# EEPROM_breakout.net
KiCad netlist of a schematic drawn in EAGLE
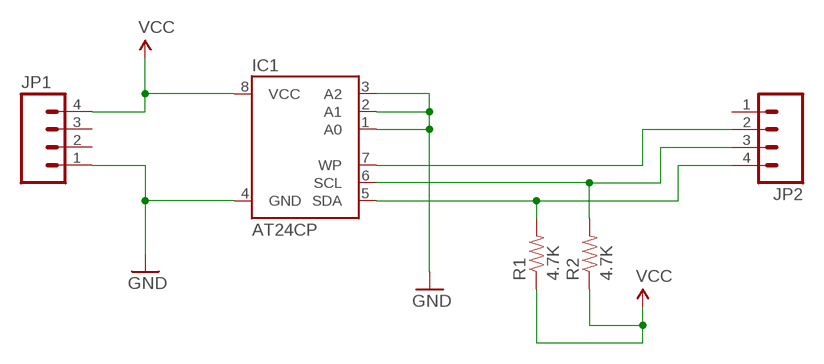
[diagram p0: schematic, sheet 1]

(export (version "E")
  (design (tool "Eeschema 10.0.6"))
  (components
    (comp (ref "IC1")
      (value "AT24CP")
      (footprint "eagle-import:DIL08")
      (fields (field (name "MPN") "AT24C1024BW-SH-B"))
      (libsource (lib "eagle-import") (part "AT24CP"))
    )
    (comp (ref "JP1")
      (value "M04LOCK")
      (footprint "eagle-import:1X04_LOCK")
      (libsource (lib "eagle-import") (part "M04LOCK"))
    )
    (comp (ref "JP2")
      (value "M04LOCK")
      (footprint "eagle-import:1X04_LOCK")
      (libsource (lib "eagle-import") (part "M04LOCK"))
    )
    (comp (ref "R1")
      (value "4.7K")
      (footprint "eagle-import:AXIAL-0.4")
      (libsource (lib "eagle-import") (part "RESISTORPTH-1/4W"))
    )
    (comp (ref "R2")
      (value "4.7K")
      (footprint "eagle-import:AXIAL-0.4")
      (libsource (lib "eagle-import") (part "RESISTORPTH-1/4W"))
    )
  )
  (nets
    (net (code "1") (name "GND") (class "Default")
      (node (ref "IC1") (pin "1") (pinfunction "A0_1") (pintype "input"))
      (node (ref "IC1") (pin "2") (pinfunction "A1_2") (pintype "input"))
      (node (ref "IC1") (pin "3") (pinfunction "A2_3") (pintype "input"))
      (node (ref "IC1") (pin "4") (pinfunction "GND_4") (pintype "power_in"))
      (node (ref "JP1") (pin "1") (pinfunction "1_1") (pintype "passive"))
    )
    (net (code "2") (name "Net-(IC1-SCL)") (class "Default")
      (node (ref "IC1") (pin "6") (pinfunction "SCL_6") (pintype "bidirectional"))
      (node (ref "JP2") (pin "3") (pinfunction "3_3") (pintype "passive"))
      (node (ref "R2") (pin "P$2") (pinfunction "2_P$2") (pintype "passive"))
    )
    (net (code "3") (name "Net-(IC1-SDA)") (class "Default")
      (node (ref "IC1") (pin "5") (pinfunction "SDA_5") (pintype "bidirectional"))
      (node (ref "JP2") (pin "4") (pinfunction "4_4") (pintype "passive"))
      (node (ref "R1") (pin "P$2") (pinfunction "2_P$2") (pintype "passive"))
    )
    (net (code "4") (name "Net-(IC1-WP)") (class "Default")
      (node (ref "IC1") (pin "7") (pinfunction "WP_7") (pintype "input"))
      (node (ref "JP2") (pin "2") (pinfunction "2_2") (pintype "passive"))
    )
    (net (code "5") (name "VCC") (class "Default")
      (node (ref "IC1") (pin "8") (pinfunction "VCC_8") (pintype "power_in"))
      (node (ref "JP1") (pin "4") (pinfunction "4_4") (pintype "passive"))
      (node (ref "R1") (pin "P$1") (pinfunction "1_P$1") (pintype "passive"))
      (node (ref "R2") (pin "P$1") (pinfunction "1_P$1") (pintype "passive"))
    )
    (net (code "6") (name "unconnected-(JP1-Pad2)") (class "Default")
      (node (ref "JP1") (pin "2") (pinfunction "2_2") (pintype "passive"))
    )
    (net (code "7") (name "unconnected-(JP1-Pad3)") (class "Default")
      (node (ref "JP1") (pin "3") (pinfunction "3_3") (pintype "passive"))
    )
    (net (code "8") (name "unconnected-(JP2-Pad1)") (class "Default")
      (node (ref "JP2") (pin "1") (pinfunction "1_1") (pintype "passive"))
    )
  )
)
